# Sheet2.net
KiCad netlist of a schematic drawn in Altium Designer
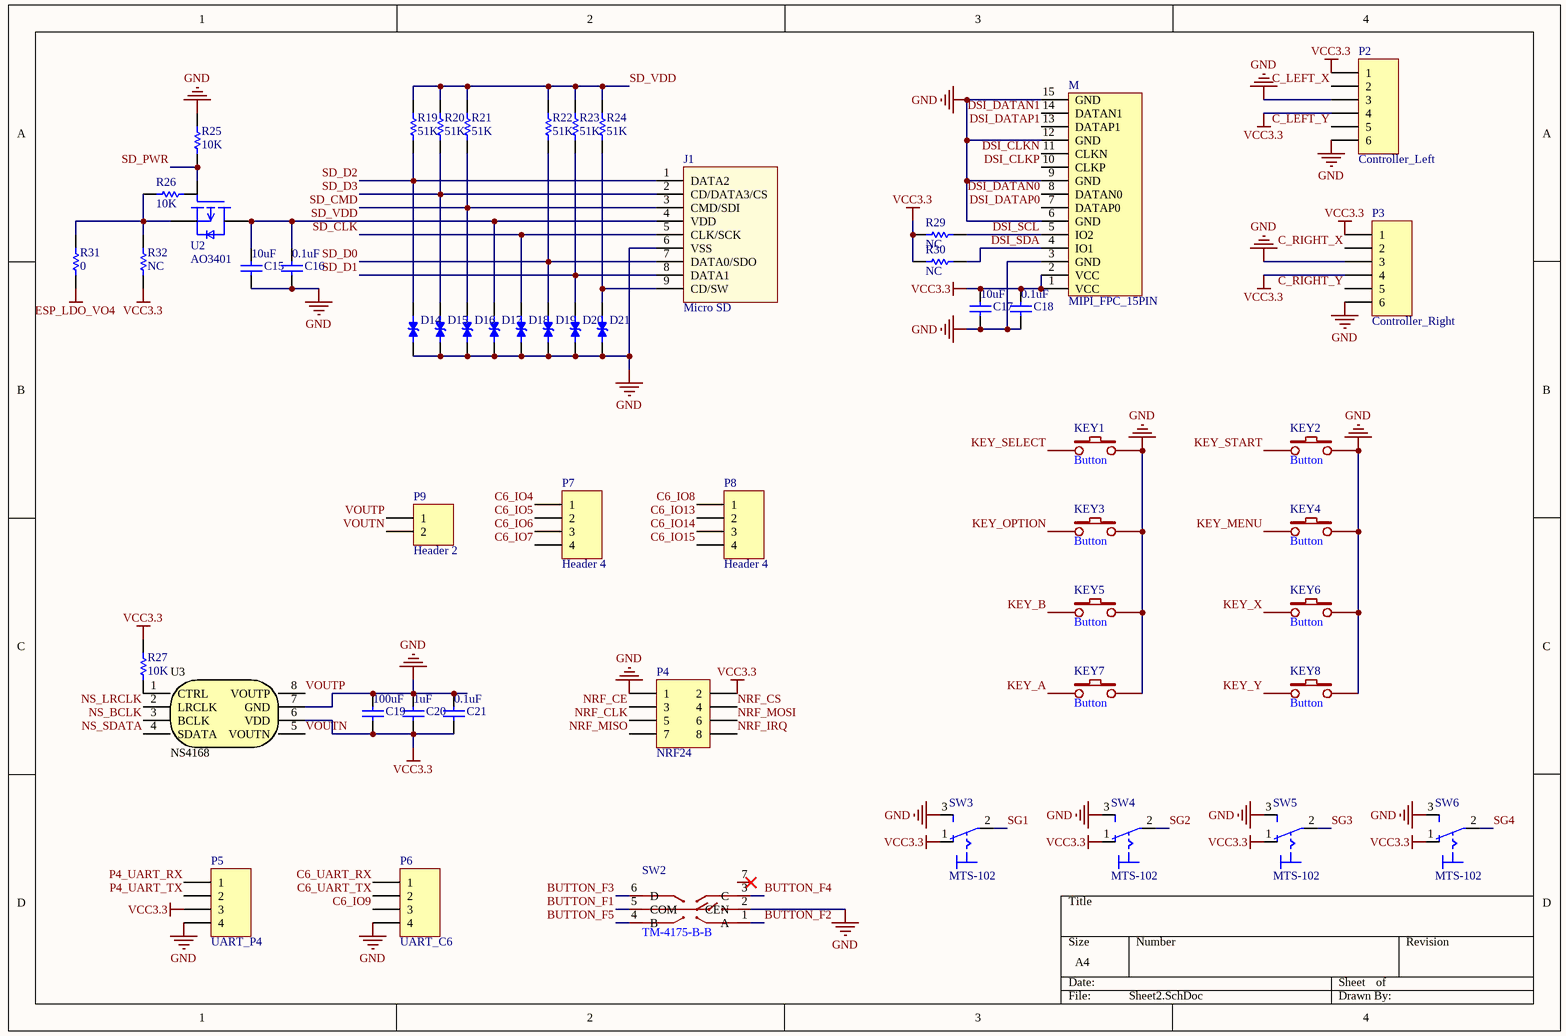
[diagram p0: Sheet2.SchDoc]

(export (version "E")
  (design (tool "Eeschema 10.0.6"))
  (components
    (comp (ref "C15")
      (value "10uF")
      (footprint "C0805")
      (description "Capacitor")
      (fields (field (name "Comment") "10uF/25v(20%)") (field (name "PUBLISHER") "Altium Limited"))
      (libsource (lib "Miscellaneous Devices") (part "Cap"))
    )
    (comp (ref "C16")
      (value "0.1uF")
      (footprint "C0805")
      (description "Capacitor")
      (fields (field (name "Comment") "0.1uF/50V(10%)") (field (name "PUBLISHER") "Altium Limited"))
      (libsource (lib "Miscellaneous Devices") (part "Cap"))
    )
    (comp (ref "C17")
      (value "10uF")
      (footprint "C0805")
      (description "Capacitor")
      (fields (field (name "Comment") "10uF/25v(20%)") (field (name "PUBLISHER") "Altium Limited"))
      (libsource (lib "Miscellaneous Devices") (part "Cap"))
    )
    (comp (ref "C18")
      (value "0.1uF")
      (footprint "C0805")
      (description "Capacitor")
      (fields (field (name "Comment") "0.1uF/50V(10%)") (field (name "PUBLISHER") "Altium Limited"))
      (libsource (lib "Miscellaneous Devices") (part "Cap"))
    )
    (comp (ref "C19")
      (value "100uF")
      (footprint "C1206")
      (description "Capacitor")
      (fields (field (name "PUBLISHER") "Altium Limited"))
      (libsource (lib "Miscellaneous Devices") (part "Cap"))
    )
    (comp (ref "C20")
      (value "1uF")
      (footprint "C0805")
      (description "Capacitor")
      (fields (field (name "PUBLISHER") "Altium Limited"))
      (libsource (lib "Miscellaneous Devices") (part "Cap"))
    )
    (comp (ref "C21")
      (value "0.1uF")
      (footprint "C0805")
      (description "Capacitor")
      (fields (field (name "Comment") "0.1uF/50V(10%)") (field (name "PUBLISHER") "Altium Limited"))
      (libsource (lib "Miscellaneous Devices") (part "Cap"))
    )
    (comp (ref "D14")
      (value "~")
      (footprint "TVS_LESD5D5.0CT1G")
      (description "Transient Voltage Suppressors for ESD Protection")
      (fields (field (name "MF") "Leshan Radio Co.") (field (name "MP") "LESD5D5.0CT1G"))
      (libsource (lib "welkin_lib_v1.0") (part "LESD5D5.0CT1G"))
    )
    (comp (ref "D15")
      (value "~")
      (footprint "TVS_LESD5D5.0CT1G")
      (description "Transient Voltage Suppressors for ESD Protection")
      (fields (field (name "MF") "Leshan Radio Co.") (field (name "MP") "LESD5D5.0CT1G"))
      (libsource (lib "welkin_lib_v1.0") (part "LESD5D5.0CT1G"))
    )
    (comp (ref "D16")
      (value "~")
      (footprint "TVS_LESD5D5.0CT1G")
      (description "Transient Voltage Suppressors for ESD Protection")
      (fields (field (name "MF") "Leshan Radio Co.") (field (name "MP") "LESD5D5.0CT1G"))
      (libsource (lib "welkin_lib_v1.0") (part "LESD5D5.0CT1G"))
    )
    (comp (ref "D17")
      (value "~")
      (footprint "TVS_LESD5D5.0CT1G")
      (description "Transient Voltage Suppressors for ESD Protection")
      (fields (field (name "MF") "Leshan Radio Co.") (field (name "MP") "LESD5D5.0CT1G"))
      (libsource (lib "welkin_lib_v1.0") (part "LESD5D5.0CT1G"))
    )
    (comp (ref "D18")
      (value "~")
      (footprint "TVS_LESD5D5.0CT1G")
      (description "Transient Voltage Suppressors for ESD Protection")
      (fields (field (name "MF") "Leshan Radio Co.") (field (name "MP") "LESD5D5.0CT1G"))
      (libsource (lib "welkin_lib_v1.0") (part "LESD5D5.0CT1G"))
    )
    (comp (ref "D19")
      (value "~")
      (footprint "TVS_LESD5D5.0CT1G")
      (description "Transient Voltage Suppressors for ESD Protection")
      (fields (field (name "MF") "Leshan Radio Co.") (field (name "MP") "LESD5D5.0CT1G"))
      (libsource (lib "welkin_lib_v1.0") (part "LESD5D5.0CT1G"))
    )
    (comp (ref "D20")
      (value "~")
      (footprint "TVS_LESD5D5.0CT1G")
      (description "Transient Voltage Suppressors for ESD Protection")
      (fields (field (name "MF") "Leshan Radio Co.") (field (name "MP") "LESD5D5.0CT1G"))
      (libsource (lib "welkin_lib_v1.0") (part "LESD5D5.0CT1G"))
    )
    (comp (ref "D21")
      (value "~")
      (footprint "TVS_LESD5D5.0CT1G")
      (description "Transient Voltage Suppressors for ESD Protection")
      (fields (field (name "MF") "Leshan Radio Co.") (field (name "MP") "LESD5D5.0CT1G"))
      (libsource (lib "welkin_lib_v1.0") (part "LESD5D5.0CT1G"))
    )
    (comp (ref "J1")
      (value "Micro SD")
      (footprint "Micro SD")
      (description "Micro SD卡")
      (fields (field (name "版权归属") "源创客"))
      (libsource (lib "welkin_lib_v1.0") (part "Micro SD"))
    )
    (comp (ref "KEY1")
      (value "Button")
      (footprint "SWITCH-A6")
      (description "A6按键")
      (fields (field (name "MANUFACTURER") "韩国韩荣") (field (name "MANUFACTURER PART") "K2-1817UQ-C4SW-01"))
      (libsource (lib "welkin_lib_v1.0") (part "Button"))
    )
    (comp (ref "KEY2")
      (value "Button")
      (footprint "SWITCH-A6")
      (description "A6按键")
      (fields (field (name "MANUFACTURER") "韩国韩荣") (field (name "MANUFACTURER PART") "K2-1817UQ-C4SW-01"))
      (libsource (lib "welkin_lib_v1.0") (part "Button"))
    )
    (comp (ref "KEY3")
      (value "Button")
      (footprint "SWITCH-A6")
      (description "A6按键")
      (fields (field (name "MANUFACTURER") "韩国韩荣") (field (name "MANUFACTURER PART") "K2-1817UQ-C4SW-01"))
      (libsource (lib "welkin_lib_v1.0") (part "Button"))
    )
    (comp (ref "KEY4")
      (value "Button")
      (footprint "SWITCH-A6")
      (description "A6按键")
      (fields (field (name "MANUFACTURER") "韩国韩荣") (field (name "MANUFACTURER PART") "K2-1817UQ-C4SW-01"))
      (libsource (lib "welkin_lib_v1.0") (part "Button"))
    )
    (comp (ref "KEY5")
      (value "Button")
      (footprint "SWITCH-A6")
      (description "A6按键")
      (fields (field (name "MANUFACTURER") "韩国韩荣") (field (name "MANUFACTURER PART") "K2-1817UQ-C4SW-01"))
      (libsource (lib "welkin_lib_v1.0") (part "Button"))
    )
    (comp (ref "KEY6")
      (value "Button")
      (footprint "SWITCH-A6")
      (description "A6按键")
      (fields (field (name "MANUFACTURER") "韩国韩荣") (field (name "MANUFACTURER PART") "K2-1817UQ-C4SW-01"))
      (libsource (lib "welkin_lib_v1.0") (part "Button"))
    )
    (comp (ref "KEY7")
      (value "Button")
      (footprint "SWITCH-A6")
      (description "A6按键")
      (fields (field (name "MANUFACTURER") "韩国韩荣") (field (name "MANUFACTURER PART") "K2-1817UQ-C4SW-01"))
      (libsource (lib "welkin_lib_v1.0") (part "Button"))
    )
    (comp (ref "KEY8")
      (value "Button")
      (footprint "SWITCH-A6")
      (description "A6按键")
      (fields (field (name "MANUFACTURER") "韩国韩荣") (field (name "MANUFACTURER PART") "K2-1817UQ-C4SW-01"))
      (libsource (lib "welkin_lib_v1.0") (part "Button"))
    )
    (comp (ref "M")
      (value "MIPI_FPC_15PIN")
      (footprint "FPC-SMD_15P-P1.00_HDGC_1.0K-GT-15PB")
      (description "立式")
      (libsource (lib "welkin_lib_v1.0") (part "MIPI_FPC_15PIN"))
    )
    (comp (ref "P2")
      (value "Controller_Left")
      (footprint "PH2.0-6P - SMT")
      (description "Header, 6-Pin")
      (fields (field (name "PUBLISHER") "Altium Limited"))
      (libsource (lib "Miscellaneous Connectors") (part "Header 6"))
    )
    (comp (ref "P3")
      (value "Controller_Right")
      (footprint "PH2.0-6P - SMT")
      (description "Header, 6-Pin")
      (fields (field (name "PUBLISHER") "Altium Limited"))
      (libsource (lib "Miscellaneous Connectors") (part "Header 6"))
    )
    (comp (ref "P4")
      (value "NRF24")
      (footprint "NRF24")
      (description "Header, 4-Pin, Dual row")
      (fields (field (name "PUBLISHER") "Altium Limited"))
      (libsource (lib "Miscellaneous Connectors") (part "Header 4X2"))
    )
    (comp (ref "P5")
      (value "UART_P4")
      (footprint "HDR1X4")
      (description "Header, 4-Pin")
      (fields (field (name "PUBLISHER") "Altium Limited"))
      (libsource (lib "Miscellaneous Connectors") (part "Header 4"))
    )
    (comp (ref "P6")
      (value "UART_C6")
      (footprint "HDR1X4")
      (description "Header, 4-Pin")
      (fields (field (name "PUBLISHER") "Altium Limited"))
      (libsource (lib "Miscellaneous Connectors") (part "Header 4"))
    )
    (comp (ref "P7")
      (value "Header 4")
      (footprint "HDR1X4")
      (description "Header, 4-Pin")
      (fields (field (name "PUBLISHER") "Altium Limited"))
      (libsource (lib "Miscellaneous Connectors") (part "Header 4"))
    )
    (comp (ref "P8")
      (value "Header 4")
      (footprint "HDR1X4")
      (description "Header, 4-Pin")
      (fields (field (name "PUBLISHER") "Altium Limited"))
      (libsource (lib "Miscellaneous Connectors") (part "Header 4"))
    )
    (comp (ref "P9")
      (value "Header 2")
      (footprint "XH2.54-2P")
      (description "Header, 2-Pin")
      (fields (field (name "PUBLISHER") "Altium Limited"))
      (libsource (lib "Miscellaneous Connectors") (part "Header 2"))
    )
    (comp (ref "R19")
      (value "51K")
      (footprint "C0805")
      (description "Resistor")
      (fields (field (name "PUBLISHER") "Altium Limited"))
      (libsource (lib "Miscellaneous Devices") (part "Res1"))
    )
    (comp (ref "R20")
      (value "51K")
      (footprint "C0805")
      (description "Resistor")
      (fields (field (name "PUBLISHER") "Altium Limited"))
      (libsource (lib "Miscellaneous Devices") (part "Res1"))
    )
    (comp (ref "R21")
      (value "51K")
      (footprint "C0805")
      (description "Resistor")
      (fields (field (name "PUBLISHER") "Altium Limited"))
      (libsource (lib "Miscellaneous Devices") (part "Res1"))
    )
    (comp (ref "R22")
      (value "51K")
      (footprint "C0805")
      (description "Resistor")
      (fields (field (name "PUBLISHER") "Altium Limited"))
      (libsource (lib "Miscellaneous Devices") (part "Res1"))
    )
    (comp (ref "R23")
      (value "51K")
      (footprint "C0805")
      (description "Resistor")
      (fields (field (name "PUBLISHER") "Altium Limited"))
      (libsource (lib "Miscellaneous Devices") (part "Res1"))
    )
    (comp (ref "R24")
      (value "51K")
      (footprint "C0805")
      (description "Resistor")
      (fields (field (name "PUBLISHER") "Altium Limited"))
      (libsource (lib "Miscellaneous Devices") (part "Res1"))
    )
    (comp (ref "R25")
      (value "10K")
      (footprint "C0805")
      (description "Resistor")
      (fields (field (name "PUBLISHER") "Altium Limited"))
      (libsource (lib "Miscellaneous Devices") (part "Res1"))
    )
    (comp (ref "R26")
      (value "10K")
      (footprint "C0805")
      (description "Resistor")
      (fields (field (name "PUBLISHER") "Altium Limited"))
      (libsource (lib "Miscellaneous Devices") (part "Res1"))
    )
    (comp (ref "R27")
      (value "10K")
      (footprint "C0805")
      (description "Resistor")
      (fields (field (name "PUBLISHER") "Altium Limited"))
      (libsource (lib "Miscellaneous Devices") (part "Res1"))
    )
    (comp (ref "R29")
      (value "NC")
      (footprint "C0805")
      (description "Resistor")
      (fields (field (name "PUBLISHER") "Altium Limited"))
      (libsource (lib "Miscellaneous Devices") (part "Res1"))
    )
    (comp (ref "R30")
      (value "NC")
      (footprint "C0805")
      (description "Resistor")
      (fields (field (name "PUBLISHER") "Altium Limited"))
      (libsource (lib "Miscellaneous Devices") (part "Res1"))
    )
    (comp (ref "R31")
      (value "0")
      (footprint "C0805")
      (description "Resistor")
      (fields (field (name "PUBLISHER") "Altium Limited"))
      (libsource (lib "Miscellaneous Devices") (part "Res1"))
    )
    (comp (ref "R32")
      (value "NC")
      (footprint "C0805")
      (description "Resistor")
      (fields (field (name "PUBLISHER") "Altium Limited"))
      (libsource (lib "Miscellaneous Devices") (part "Res1"))
    )
    (comp (ref "SW2")
      (value "TM-4175-B-B")
      (footprint "TM4175-B-B")
      (fields (field (name "MANUFACTURER") "XKB Connectivity(中国星坤)"))
      (libsource (lib "welkin_lib_v1.0") (part "TM-4175-B-B"))
    )
    (comp (ref "SW3")
      (value "MTS-102")
      (footprint "MTS-102")
      (description "Rectangular Cable Assemblies .100 Mini Mate Single Row Discrete Wire Cable Assembly, Terminal")
      (fields (field (name "MF") "Motorola") (field (name "MP") "MTS102"))
      (libsource (lib "welkin_lib_v1.0") (part "MTS-102"))
    )
    (comp (ref "SW4")
      (value "MTS-102")
      (footprint "MTS-102")
      (description "Rectangular Cable Assemblies .100 Mini Mate Single Row Discrete Wire Cable Assembly, Terminal")
      (fields (field (name "MF") "Motorola") (field (name "MP") "MTS102"))
      (libsource (lib "welkin_lib_v1.0") (part "MTS-102"))
    )
    (comp (ref "SW5")
      (value "MTS-102")
      (footprint "MTS-102")
      (description "Rectangular Cable Assemblies .100 Mini Mate Single Row Discrete Wire Cable Assembly, Terminal")
      (fields (field (name "MF") "Motorola") (field (name "MP") "MTS102"))
      (libsource (lib "welkin_lib_v1.0") (part "MTS-102"))
    )
    (comp (ref "SW6")
      (value "MTS-102")
      (footprint "MTS-102")
      (description "Rectangular Cable Assemblies .100 Mini Mate Single Row Discrete Wire Cable Assembly, Terminal")
      (fields (field (name "MF") "Motorola") (field (name "MP") "MTS102"))
      (libsource (lib "welkin_lib_v1.0") (part "MTS-102"))
    )
    (comp (ref "U2")
      (value "AO3401")
      (footprint "A03401")
      (description "P-Channel 30 V 4A (Ta) 1.4W (Ta) Surface Mount SOT-23-3")
      (fields (field (name "MF") "Alpha & Omega Semiconductor"))
      (libsource (lib "welkin_lib_v1.0") (part "AO3401"))
    )
    (comp (ref "U3")
      (value "NS4168")
      (footprint "NS4168")
      (libsource (lib "welkin_lib_v1.0") (part "NS4168"))
    )
  )
  (nets
    (net (code "1") (name "/BUTTON_F1") (class "Default")
      (node (ref "SW2") (pin "5") (pinfunction "COM_5") (pintype "passive"))
    )
    (net (code "2") (name "/BUTTON_F2") (class "Default")
      (node (ref "SW2") (pin "1") (pinfunction "A_1") (pintype "passive"))
    )
    (net (code "3") (name "/BUTTON_F3") (class "Default")
      (node (ref "SW2") (pin "6") (pinfunction "D_6") (pintype "passive"))
    )
    (net (code "4") (name "/BUTTON_F4") (class "Default")
      (node (ref "SW2") (pin "3") (pinfunction "C_3") (pintype "passive"))
    )
    (net (code "5") (name "/BUTTON_F5") (class "Default")
      (node (ref "SW2") (pin "4") (pinfunction "B_4") (pintype "passive"))
    )
    (net (code "6") (name "/C6_IO4") (class "Default")
      (node (ref "P7") (pin "1") (pinfunction "1_1") (pintype "passive"))
    )
    (net (code "7") (name "/C6_IO5") (class "Default")
      (node (ref "P7") (pin "2") (pinfunction "2_2") (pintype "passive"))
    )
    (net (code "8") (name "/C6_IO6") (class "Default")
      (node (ref "P7") (pin "3") (pinfunction "3_3") (pintype "passive"))
    )
    (net (code "9") (name "/C6_IO7") (class "Default")
      (node (ref "P7") (pin "4") (pinfunction "4_4") (pintype "passive"))
    )
    (net (code "10") (name "/C6_IO8") (class "Default")
      (node (ref "P8") (pin "1") (pinfunction "1_1") (pintype "passive"))
    )
    (net (code "11") (name "/C6_IO9") (class "Default")
      (node (ref "P6") (pin "3") (pinfunction "3_3") (pintype "passive"))
    )
    (net (code "12") (name "/C6_IO13") (class "Default")
      (node (ref "P8") (pin "2") (pinfunction "2_2") (pintype "passive"))
    )
    (net (code "13") (name "/C6_IO14") (class "Default")
      (node (ref "P8") (pin "3") (pinfunction "3_3") (pintype "passive"))
    )
    (net (code "14") (name "/C6_IO15") (class "Default")
      (node (ref "P8") (pin "4") (pinfunction "4_4") (pintype "passive"))
    )
    (net (code "15") (name "/C6_UART_RX") (class "Default")
      (node (ref "P6") (pin "1") (pinfunction "1_1") (pintype "passive"))
    )
    (net (code "16") (name "/C6_UART_TX") (class "Default")
      (node (ref "P6") (pin "2") (pinfunction "2_2") (pintype "passive"))
    )
    (net (code "17") (name "/C_LEFT_X") (class "Default")
      (node (ref "P2") (pin "2") (pinfunction "2_2") (pintype "passive"))
    )
    (net (code "18") (name "/C_LEFT_Y") (class "Default")
      (node (ref "P2") (pin "5") (pinfunction "5_5") (pintype "passive"))
    )
    (net (code "19") (name "/C_RIGHT_X") (class "Default")
      (node (ref "P3") (pin "2") (pinfunction "2_2") (pintype "passive"))
    )
    (net (code "20") (name "/C_RIGHT_Y") (class "Default")
      (node (ref "P3") (pin "5") (pinfunction "5_5") (pintype "passive"))
    )
    (net (code "21") (name "/DSI_CLKN") (class "Default")
      (node (ref "M") (pin "11") (pinfunction "CLKN_11") (pintype "passive"))
    )
    (net (code "22") (name "/DSI_CLKP") (class "Default")
      (node (ref "M") (pin "10") (pinfunction "CLKP_10") (pintype "passive"))
    )
    (net (code "23") (name "/DSI_DATAN0") (class "Default")
      (node (ref "M") (pin "8") (pinfunction "DATAN0_8") (pintype "passive"))
    )
    (net (code "24") (name "/DSI_DATAN1") (class "Default")
      (node (ref "M") (pin "14") (pinfunction "DATAN1_14") (pintype "passive"))
    )
    (net (code "25") (name "/DSI_DATAP0") (class "Default")
      (node (ref "M") (pin "7") (pinfunction "DATAP0_7") (pintype "passive"))
    )
    (net (code "26") (name "/DSI_DATAP1") (class "Default")
      (node (ref "M") (pin "13") (pinfunction "DATAP1_13") (pintype "passive"))
    )
    (net (code "27") (name "/DSI_SCL") (class "Default")
      (node (ref "M") (pin "5") (pinfunction "IO2_5") (pintype "passive"))
      (node (ref "R29") (pin "1") (pinfunction "1_1") (pintype "passive"))
    )
    (net (code "28") (name "/DSI_SDA") (class "Default")
      (node (ref "M") (pin "4") (pinfunction "IO1_4") (pintype "passive"))
      (node (ref "R30") (pin "1") (pinfunction "1_1") (pintype "passive"))
    )
    (net (code "29") (name "/KEY_A") (class "Default")
      (node (ref "KEY7") (pin "1") (pinfunction "1_1") (pintype "passive"))
    )
    (net (code "30") (name "/KEY_B") (class "Default")
      (node (ref "KEY5") (pin "1") (pinfunction "1_1") (pintype "passive"))
    )
    (net (code "31") (name "/KEY_MENU") (class "Default")
      (node (ref "KEY4") (pin "1") (pinfunction "1_1") (pintype "passive"))
    )
    (net (code "32") (name "/KEY_OPTION") (class "Default")
      (node (ref "KEY3") (pin "1") (pinfunction "1_1") (pintype "passive"))
    )
    (net (code "33") (name "/KEY_SELECT") (class "Default")
      (node (ref "KEY1") (pin "1") (pinfunction "1_1") (pintype "passive"))
    )
    (net (code "34") (name "/KEY_START") (class "Default")
      (node (ref "KEY2") (pin "1") (pinfunction "1_1") (pintype "passive"))
    )
    (net (code "35") (name "/KEY_X") (class "Default")
      (node (ref "KEY6") (pin "1") (pinfunction "1_1") (pintype "passive"))
    )
    (net (code "36") (name "/KEY_Y") (class "Default")
      (node (ref "KEY8") (pin "1") (pinfunction "1_1") (pintype "passive"))
    )
    (net (code "37") (name "/NRF_CE") (class "Default")
      (node (ref "P4") (pin "3") (pinfunction "3_3") (pintype "passive"))
    )
    (net (code "38") (name "/NRF_CLK") (class "Default")
      (node (ref "P4") (pin "5") (pinfunction "5_5") (pintype "passive"))
    )
    (net (code "39") (name "/NRF_CS") (class "Default")
      (node (ref "P4") (pin "4") (pinfunction "4_4") (pintype "passive"))
    )
    (net (code "40") (name "/NRF_IRQ") (class "Default")
      (node (ref "P4") (pin "8") (pinfunction "8_8") (pintype "passive"))
    )
    (net (code "41") (name "/NRF_MISO") (class "Default")
      (node (ref "P4") (pin "7") (pinfunction "7_7") (pintype "passive"))
    )
    (net (code "42") (name "/NRF_MOSI") (class "Default")
      (node (ref "P4") (pin "6") (pinfunction "6_6") (pintype "passive"))
    )
    (net (code "43") (name "/NS_BCLK") (class "Default")
      (node (ref "U3") (pin "3") (pinfunction "BCLK_3") (pintype "passive"))
    )
    (net (code "44") (name "/NS_LRCLK") (class "Default")
      (node (ref "U3") (pin "2") (pinfunction "LRCLK_2") (pintype "passive"))
    )
    (net (code "45") (name "/NS_SDATA") (class "Default")
      (node (ref "U3") (pin "4") (pinfunction "SDATA_4") (pintype "passive"))
    )
    (net (code "46") (name "/P4_UART_RX") (class "Default")
      (node (ref "P5") (pin "1") (pinfunction "1_1") (pintype "passive"))
    )
    (net (code "47") (name "/P4_UART_TX") (class "Default")
      (node (ref "P5") (pin "2") (pinfunction "2_2") (pintype "passive"))
    )
    (net (code "48") (name "/SD_CLK") (class "Default")
      (node (ref "D18") (pin "2") (pinfunction "2_2") (pintype "passive"))
      (node (ref "J1") (pin "5") (pinfunction "CLK/SCK_5") (pintype "passive"))
    )
    (net (code "49") (name "/SD_CMD") (class "Default")
      (node (ref "D16") (pin "2") (pinfunction "2_2") (pintype "passive"))
      (node (ref "J1") (pin "3") (pinfunction "CMD/SDI_3") (pintype "passive"))
      (node (ref "R21") (pin "2") (pinfunction "2_2") (pintype "passive"))
    )
    (net (code "50") (name "/SD_D0") (class "Default")
      (node (ref "D19") (pin "2") (pinfunction "2_2") (pintype "passive"))
      (node (ref "J1") (pin "7") (pinfunction "DATA0/SDO_7") (pintype "passive"))
      (node (ref "R22") (pin "2") (pinfunction "2_2") (pintype "passive"))
    )
    (net (code "51") (name "/SD_D1") (class "Default")
      (node (ref "D20") (pin "2") (pinfunction "2_2") (pintype "passive"))
      (node (ref "J1") (pin "8") (pinfunction "DATA1_8") (pintype "passive"))
      (node (ref "R23") (pin "2") (pinfunction "2_2") (pintype "passive"))
    )
    (net (code "52") (name "/SD_D2") (class "Default")
      (node (ref "D14") (pin "2") (pinfunction "2_2") (pintype "passive"))
      (node (ref "J1") (pin "1") (pinfunction "DATA2_1") (pintype "passive"))
      (node (ref "R19") (pin "2") (pinfunction "2_2") (pintype "passive"))
    )
    (net (code "53") (name "/SD_D3") (class "Default")
      (node (ref "D15") (pin "2") (pinfunction "2_2") (pintype "passive"))
      (node (ref "J1") (pin "2") (pinfunction "CD/DATA3/CS_2") (pintype "passive"))
      (node (ref "R20") (pin "2") (pinfunction "2_2") (pintype "passive"))
    )
    (net (code "54") (name "/SD_PWR") (class "Default")
      (node (ref "R25") (pin "2") (pinfunction "2_2") (pintype "passive"))
      (node (ref "U2") (pin "1") (pinfunction "G_1") (pintype "passive"))
    )
    (net (code "55") (name "/SD_VDD") (class "Default")
      (node (ref "C15") (pin "2") (pinfunction "2_2") (pintype "passive"))
      (node (ref "C16") (pin "2") (pinfunction "2_2") (pintype "passive"))
      (node (ref "D17") (pin "2") (pinfunction "2_2") (pintype "passive"))
      (node (ref "J1") (pin "4") (pinfunction "VDD_4") (pintype "passive"))
      (node (ref "R19") (pin "1") (pinfunction "1_1") (pintype "passive"))
      (node (ref "R20") (pin "1") (pinfunction "1_1") (pintype "passive"))
      (node (ref "R21") (pin "1") (pinfunction "1_1") (pintype "passive"))
      (node (ref "R22") (pin "1") (pinfunction "1_1") (pintype "passive"))
      (node (ref "R23") (pin "1") (pinfunction "1_1") (pintype "passive"))
      (node (ref "R24") (pin "1") (pinfunction "1_1") (pintype "passive"))
      (node (ref "U2") (pin "3") (pinfunction "D_3") (pintype "passive"))
    )
    (net (code "56") (name "/SG1") (class "Default")
      (node (ref "SW3") (pin "2") (pinfunction "P_2") (pintype "passive"))
    )
    (net (code "57") (name "/SG2") (class "Default")
      (node (ref "SW4") (pin "2") (pinfunction "P_2") (pintype "passive"))
    )
    (net (code "58") (name "/SG3") (class "Default")
      (node (ref "SW5") (pin "2") (pinfunction "P_2") (pintype "passive"))
    )
    (net (code "59") (name "/SG4") (class "Default")
      (node (ref "SW6") (pin "2") (pinfunction "P_2") (pintype "passive"))
    )
    (net (code "60") (name "/VOUTN") (class "Default")
      (node (ref "P9") (pin "2") (pinfunction "2_2") (pintype "passive"))
      (node (ref "U3") (pin "5") (pinfunction "VOUTN_5") (pintype "passive"))
    )
    (net (code "61") (name "/VOUTP") (class "Default")
      (node (ref "P9") (pin "1") (pinfunction "1_1") (pintype "passive"))
      (node (ref "U3") (pin "8") (pinfunction "VOUTP_8") (pintype "passive"))
    )
    (net (code "62") (name "ESP_LDO_VO4") (class "Default")
      (node (ref "R31") (pin "2") (pinfunction "2_2") (pintype "passive"))
    )
    (net (code "63") (name "GND") (class "Default")
      (node (ref "C15") (pin "1") (pinfunction "1_1") (pintype "passive"))
      (node (ref "C16") (pin "1") (pinfunction "1_1") (pintype "passive"))
      (node (ref "C17") (pin "1") (pinfunction "1_1") (pintype "passive"))
      (node (ref "C18") (pin "1") (pinfunction "1_1") (pintype "passive"))
      (node (ref "C19") (pin "2") (pinfunction "2_2") (pintype "passive"))
      (node (ref "C20") (pin "2") (pinfunction "2_2") (pintype "passive"))
      (node (ref "C21") (pin "2") (pinfunction "2_2") (pintype "passive"))
      (node (ref "D14") (pin "1") (pinfunction "1_1") (pintype "passive"))
      (node (ref "D15") (pin "1") (pinfunction "1_1") (pintype "passive"))
      (node (ref "D16") (pin "1") (pinfunction "1_1") (pintype "passive"))
      (node (ref "D17") (pin "1") (pinfunction "1_1") (pintype "passive"))
      (node (ref "D18") (pin "1") (pinfunction "1_1") (pintype "passive"))
      (node (ref "D19") (pin "1") (pinfunction "1_1") (pintype "passive"))
      (node (ref "D20") (pin "1") (pinfunction "1_1") (pintype "passive"))
      (node (ref "D21") (pin "1") (pinfunction "1_1") (pintype "passive"))
      (node (ref "J1") (pin "6") (pinfunction "VSS_6") (pintype "passive"))
      (node (ref "KEY1") (pin "2") (pinfunction "2_2") (pintype "passive"))
      (node (ref "KEY2") (pin "2") (pinfunction "2_2") (pintype "passive"))
      (node (ref "KEY3") (pin "2") (pinfunction "2_2") (pintype "passive"))
      (node (ref "KEY4") (pin "2") (pinfunction "2_2") (pintype "passive"))
      (node (ref "KEY5") (pin "2") (pinfunction "2_2") (pintype "passive"))
      (node (ref "KEY6") (pin "2") (pinfunction "2_2") (pintype "passive"))
      (node (ref "KEY7") (pin "2") (pinfunction "2_2") (pintype "passive"))
      (node (ref "KEY8") (pin "2") (pinfunction "2_2") (pintype "passive"))
      (node (ref "M") (pin "12") (pinfunction "GND_12") (pintype "passive"))
      (node (ref "M") (pin "15") (pinfunction "GND_15") (pintype "passive"))
      (node (ref "M") (pin "3") (pinfunction "GND_3") (pintype "passive"))
      (node (ref "M") (pin "6") (pinfunction "GND_6") (pintype "passive"))
      (node (ref "M") (pin "9") (pinfunction "GND_9") (pintype "passive"))
      (node (ref "P2") (pin "3") (pinfunction "3_3") (pintype "passive"))
      (node (ref "P2") (pin "6") (pinfunction "6_6") (pintype "passive"))
      (node (ref "P3") (pin "3") (pinfunction "3_3") (pintype "passive"))
      (node (ref "P3") (pin "6") (pinfunction "6_6") (pintype "passive"))
      (node (ref "P4") (pin "1") (pinfunction "1_1") (pintype "passive"))
      (node (ref "P5") (pin "4") (pinfunction "4_4") (pintype "passive"))
      (node (ref "P6") (pin "4") (pinfunction "4_4") (pintype "passive"))
      (node (ref "R25") (pin "1") (pinfunction "1_1") (pintype "passive"))
      (node (ref "SW2") (pin "2") (pinfunction "CEN_2") (pintype "passive"))
      (node (ref "SW3") (pin "3") (pinfunction "S_3") (pintype "passive"))
      (node (ref "SW4") (pin "3") (pinfunction "S_3") (pintype "passive"))
      (node (ref "SW5") (pin "3") (pinfunction "S_3") (pintype "passive"))
      (node (ref "SW6") (pin "3") (pinfunction "S_3") (pintype "passive"))
      (node (ref "U3") (pin "7") (pinfunction "GND_7") (pintype "passive"))
    )
    (net (code "64") (name "Net-(J1-CD{slash}SW)") (class "Default")
      (node (ref "D21") (pin "2") (pinfunction "2_2") (pintype "passive"))
      (node (ref "J1") (pin "9") (pinfunction "CD/SW_9") (pintype "passive"))
      (node (ref "R24") (pin "2") (pinfunction "2_2") (pintype "passive"))
    )
    (net (code "65") (name "Net-(U2-S)") (class "Default")
      (node (ref "R26") (pin "1") (pinfunction "1_1") (pintype "passive"))
      (node (ref "R31") (pin "1") (pinfunction "1_1") (pintype "passive"))
      (node (ref "R32") (pin "1") (pinfunction "1_1") (pintype "passive"))
      (node (ref "U2") (pin "2") (pinfunction "S_2") (pintype "passive"))
    )
    (net (code "66") (name "Net-(U3-CTRL)") (class "Default")
      (node (ref "R27") (pin "2") (pinfunction "2_2") (pintype "passive"))
      (node (ref "U3") (pin "1") (pinfunction "CTRL_1") (pintype "passive"))
    )
    (net (code "67") (name "VCC3.3") (class "Default")
      (node (ref "C17") (pin "2") (pinfunction "2_2") (pintype "passive"))
      (node (ref "C18") (pin "2") (pinfunction "2_2") (pintype "passive"))
      (node (ref "C19") (pin "1") (pinfunction "1_1") (pintype "passive"))
      (node (ref "C20") (pin "1") (pinfunction "1_1") (pintype "passive"))
      (node (ref "C21") (pin "1") (pinfunction "1_1") (pintype "passive"))
      (node (ref "M") (pin "1") (pinfunction "VCC_1") (pintype "passive"))
      (node (ref "M") (pin "2") (pinfunction "VCC_2") (pintype "passive"))
      (node (ref "P2") (pin "1") (pinfunction "1_1") (pintype "passive"))
      (node (ref "P2") (pin "4") (pinfunction "4_4") (pintype "passive"))
      (node (ref "P3") (pin "1") (pinfunction "1_1") (pintype "passive"))
      (node (ref "P3") (pin "4") (pinfunction "4_4") (pintype "passive"))
      (node (ref "P4") (pin "2") (pinfunction "2_2") (pintype "passive"))
      (node (ref "P5") (pin "3") (pinfunction "3_3") (pintype "passive"))
      (node (ref "R27") (pin "1") (pinfunction "1_1") (pintype "passive"))
      (node (ref "R29") (pin "2") (pinfunction "2_2") (pintype "passive"))
      (node (ref "R30") (pin "2") (pinfunction "2_2") (pintype "passive"))
      (node (ref "R32") (pin "2") (pinfunction "2_2") (pintype "passive"))
      (node (ref "SW3") (pin "1") (pinfunction "O_1") (pintype "passive"))
      (node (ref "SW4") (pin "1") (pinfunction "O_1") (pintype "passive"))
      (node (ref "SW5") (pin "1") (pinfunction "O_1") (pintype "passive"))
      (node (ref "SW6") (pin "1") (pinfunction "O_1") (pintype "passive"))
      (node (ref "U3") (pin "6") (pinfunction "VDD_6") (pintype "passive"))
    )
    (net (code "68") (name "unconnected-(R26-Pad2)") (class "Default")
      (node (ref "R26") (pin "2") (pinfunction "2_2") (pintype "passive"))
    )
    (net (code "69") (name "unconnected-(SW2-Pad7)") (class "Default")
      (node (ref "SW2") (pin "7") (pintype "passive+no_connect"))
    )
  )
)
